# USB_to_Serial.net
KiCad netlist of a schematic drawn in Altium Designer
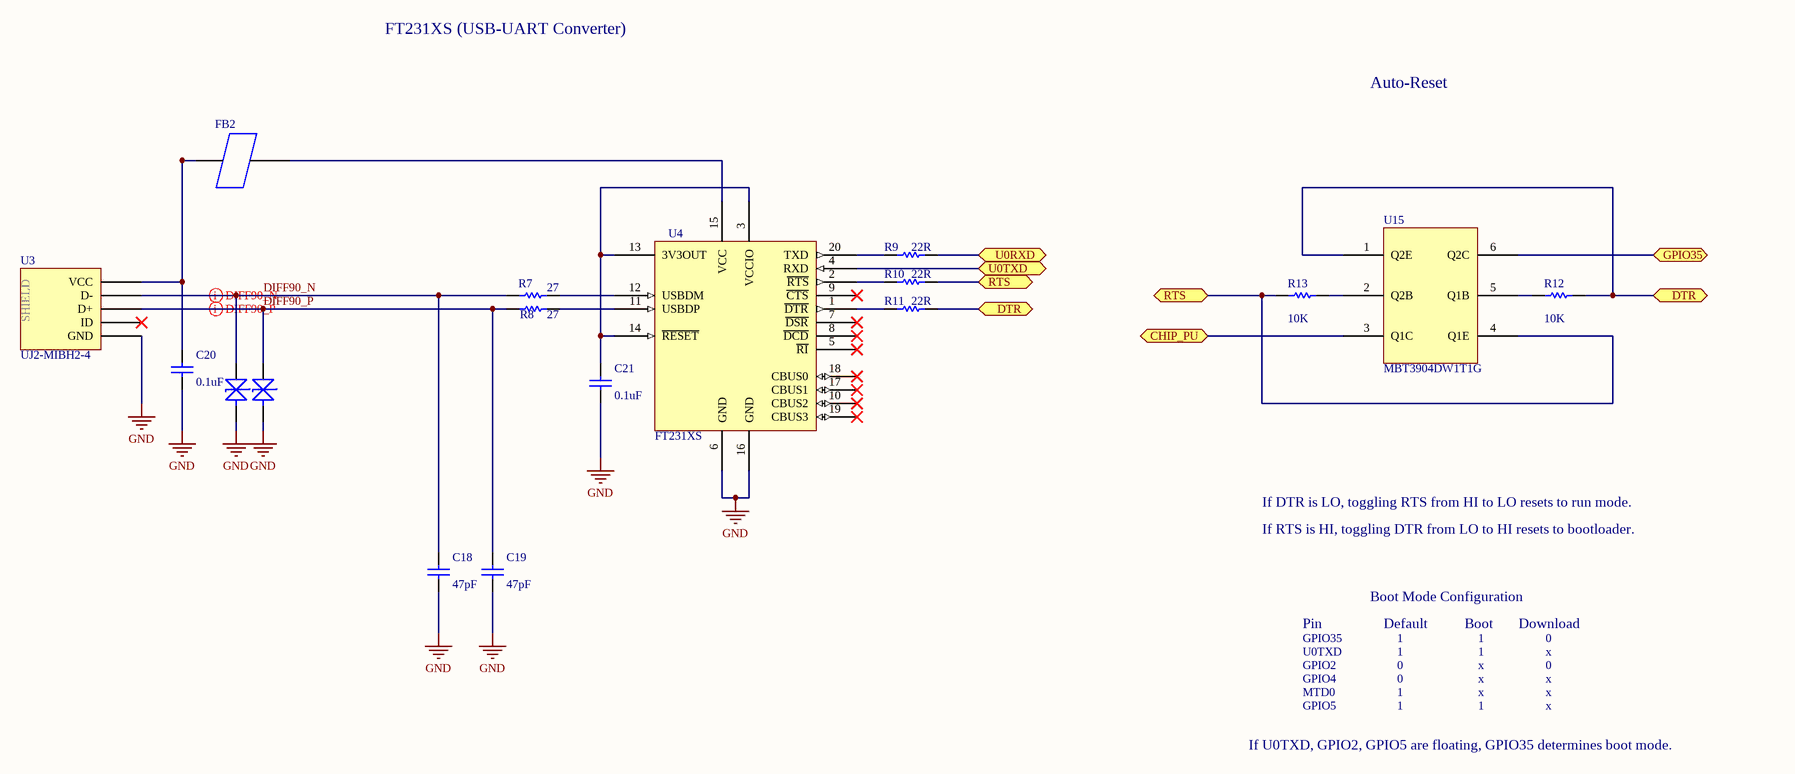
[diagram p0: USB to Serial.SchDoc]

(export (version "E")
  (design (tool "Eeschema 10.0.6"))
  (components
    (comp (ref "C18")
      (value "47pF")
      (footprint "0402")
      (description "Capacitor")
      (fields (field (name "Comment") "Cap") (field (name "PUBLISHER") "Altium Limited"))
      (libsource (lib "Miscellaneous Devices") (part "Cap"))
    )
    (comp (ref "C19")
      (value "47pF")
      (footprint "0402")
      (description "Capacitor")
      (fields (field (name "Comment") "Cap") (field (name "PUBLISHER") "Altium Limited"))
      (libsource (lib "Miscellaneous Devices") (part "Cap"))
    )
    (comp (ref "C20")
      (value "0.1uF")
      (footprint "1608[0603]")
      (description "Capacitor")
      (fields (field (name "Comment") "Cap") (field (name "PUBLISHER") "Altium Limited"))
      (libsource (lib "Miscellaneous Devices") (part "Cap"))
    )
    (comp (ref "C21")
      (value "0.1uF")
      (footprint "1608[0603]")
      (description "Capacitor")
      (fields (field (name "Comment") "Cap") (field (name "PUBLISHER") "Altium Limited"))
      (libsource (lib "Miscellaneous Devices") (part "Cap"))
    )
    (comp (ref "D2")
      (value "ESD7951ST5GOSCT-ND")
      (footprint "SODFL100X40-2N")
      (description "TVS Diode")
      (libsource (lib "Gas Monitor Components") (part "ESD7951S"))
    )
    (comp (ref "D3")
      (value "ESD7951ST5GOSCT-ND")
      (footprint "SODFL100X40-2N")
      (description "TVS Diode")
      (libsource (lib "Gas Monitor Components") (part "ESD7951S"))
    )
    (comp (ref "FB2")
      (value "Ferrite Bead")
      (footprint "MI0805K400R-10")
      (description "MI0805K400R-10")
      (libsource (lib "Gas Monitor Components") (part "Ferrite Bead"))
    )
    (comp (ref "R7")
      (value "27")
      (footprint "J1-0603")
      (description "Resistor")
      (fields (field (name "Comment") "Res1") (field (name "PUBLISHER") "Altium Limited"))
      (libsource (lib "Miscellaneous Devices") (part "Res1"))
    )
    (comp (ref "R8")
      (value "27")
      (footprint "J1-0603")
      (description "Resistor")
      (fields (field (name "Comment") "Res1") (field (name "PUBLISHER") "Altium Limited"))
      (libsource (lib "Miscellaneous Devices") (part "Res1"))
    )
    (comp (ref "R9")
      (value "22R")
      (footprint "6-0805_N")
      (description "Resistor")
      (fields (field (name "Comment") "Res1") (field (name "PUBLISHER") "Altium Limited"))
      (libsource (lib "Miscellaneous Devices") (part "Res1"))
    )
    (comp (ref "R10")
      (value "22R")
      (footprint "6-0805_N")
      (description "Resistor")
      (fields (field (name "Comment") "Res1") (field (name "PUBLISHER") "Altium Limited"))
      (libsource (lib "Miscellaneous Devices") (part "Res1"))
    )
    (comp (ref "R11")
      (value "22R")
      (footprint "6-0805_N")
      (description "Resistor")
      (fields (field (name "Comment") "Res1") (field (name "PUBLISHER") "Altium Limited"))
      (libsource (lib "Miscellaneous Devices") (part "Res1"))
    )
    (comp (ref "R12")
      (value "10K")
      (footprint "6-0805_N")
      (description "Resistor")
      (fields (field (name "Comment") "Res1") (field (name "PUBLISHER") "Altium Limited"))
      (libsource (lib "Miscellaneous Devices") (part "Res1"))
    )
    (comp (ref "R13")
      (value "10K")
      (footprint "6-0805_N")
      (description "Resistor")
      (fields (field (name "Comment") "Res1") (field (name "PUBLISHER") "Altium Limited"))
      (libsource (lib "Miscellaneous Devices") (part "Res1"))
    )
    (comp (ref "U3")
      (value "UJ2-MIBH2-4")
      (footprint "UJ2-MIBH2-4-SMT")
      (libsource (lib "Gas Monitor Components") (part "USB Shield"))
    )
    (comp (ref "U4")
      (value "FT231XS")
      (footprint "SOP64P1030X175-20N")
      (description "USB-UART Interface")
      (libsource (lib "Gas Monitor Components") (part "FT231XS"))
    )
    (comp (ref "U15")
      (value "MBT3904DW1T1G")
      (footprint "SOT65P210X110-6N")
      (description "Dual NPN Transistors")
      (libsource (lib "Gas Monitor Components") (part "MBT3904DW1"))
    )
  )
  (nets
    (net (code "1") (name "/CHIP_PU") (class "Default")
      (node (ref "U15") (pin "3") (pinfunction "Q1C_3") (pintype "passive"))
    )
    (net (code "2") (name "/DIFF90_N") (class "Default")
      (node (ref "C18") (pin "2") (pinfunction "2_2") (pintype "passive"))
      (node (ref "D2") (pin "2") (pinfunction "ANODE_2") (pintype "passive"))
      (node (ref "R7") (pin "1") (pinfunction "1_1") (pintype "passive"))
      (node (ref "U3") (pin "2") (pinfunction "D-_2") (pintype "passive"))
    )
    (net (code "3") (name "/DIFF90_P") (class "Default")
      (node (ref "C19") (pin "2") (pinfunction "2_2") (pintype "passive"))
      (node (ref "D3") (pin "2") (pinfunction "ANODE_2") (pintype "passive"))
      (node (ref "R8") (pin "1") (pinfunction "1_1") (pintype "passive"))
      (node (ref "U3") (pin "3") (pinfunction "D+_3") (pintype "passive"))
    )
    (net (code "4") (name "/DTR") (class "Default")
      (node (ref "R11") (pin "2") (pinfunction "2_2") (pintype "passive"))
      (node (ref "R12") (pin "2") (pinfunction "2_2") (pintype "passive"))
      (node (ref "U15") (pin "1") (pinfunction "Q2E_1") (pintype "passive"))
    )
    (net (code "5") (name "/GPIO35") (class "Default")
      (node (ref "U15") (pin "6") (pinfunction "Q2C_6") (pintype "passive"))
    )
    (net (code "6") (name "/RTS") (class "Default")
      (node (ref "R10") (pin "2") (pinfunction "2_2") (pintype "passive"))
      (node (ref "R13") (pin "1") (pinfunction "1_1") (pintype "passive"))
      (node (ref "U15") (pin "4") (pinfunction "Q1E_4") (pintype "passive"))
    )
    (net (code "7") (name "/U0RXD") (class "Default")
      (node (ref "R9") (pin "2") (pinfunction "2_2") (pintype "passive"))
    )
    (net (code "8") (name "/U0TXD") (class "Default")
      (node (ref "U4") (pin "4") (pinfunction "RXD_4") (pintype "input"))
    )
    (net (code "9") (name "GND") (class "Default")
      (node (ref "C18") (pin "1") (pinfunction "1_1") (pintype "passive"))
      (node (ref "C19") (pin "1") (pinfunction "1_1") (pintype "passive"))
      (node (ref "C20") (pin "1") (pinfunction "1_1") (pintype "passive"))
      (node (ref "C21") (pin "1") (pinfunction "1_1") (pintype "passive"))
      (node (ref "D2") (pin "1") (pinfunction "CATHODE_1") (pintype "passive"))
      (node (ref "D3") (pin "1") (pinfunction "CATHODE_1") (pintype "passive"))
      (node (ref "U3") (pin "5") (pinfunction "GND_5") (pintype "power_in"))
      (node (ref "U4") (pin "16") (pinfunction "GND_16") (pintype "power_in"))
      (node (ref "U4") (pin "6") (pinfunction "GND_6") (pintype "power_in"))
    )
    (net (code "10") (name "Net-(U3-VCC)") (class "Default")
      (node (ref "C20") (pin "2") (pinfunction "2_2") (pintype "passive"))
      (node (ref "FB2") (pin "1") (pinfunction "1_1") (pintype "passive"))
      (node (ref "U3") (pin "1") (pinfunction "VCC_1") (pintype "power_in"))
    )
    (net (code "11") (name "Net-(U4-3V3OUT)") (class "Default")
      (node (ref "C21") (pin "2") (pinfunction "2_2") (pintype "passive"))
      (node (ref "U4") (pin "13") (pinfunction "3V3OUT_13") (pintype "power_in"))
      (node (ref "U4") (pin "14") (pinfunction "~{RESET}_14") (pintype "input"))
      (node (ref "U4") (pin "3") (pinfunction "VCCIO_3") (pintype "passive"))
    )
    (net (code "12") (name "Net-(U4-TXD)") (class "Default")
      (node (ref "R9") (pin "1") (pinfunction "1_1") (pintype "passive"))
      (node (ref "U4") (pin "20") (pinfunction "TXD_20") (pintype "output"))
    )
    (net (code "13") (name "Net-(U4-USBDM)") (class "Default")
      (node (ref "R7") (pin "2") (pinfunction "2_2") (pintype "passive"))
      (node (ref "U4") (pin "12") (pinfunction "USBDM_12") (pintype "input"))
    )
    (net (code "14") (name "Net-(U4-USBDP)") (class "Default")
      (node (ref "R8") (pin "2") (pinfunction "2_2") (pintype "passive"))
      (node (ref "U4") (pin "11") (pinfunction "USBDP_11") (pintype "input"))
    )
    (net (code "15") (name "Net-(U4-VCC)") (class "Default")
      (node (ref "FB2") (pin "2") (pinfunction "2_2") (pintype "passive"))
      (node (ref "U4") (pin "15") (pinfunction "VCC_15") (pintype "power_in"))
    )
    (net (code "16") (name "Net-(U4-~{DTR})") (class "Default")
      (node (ref "R11") (pin "1") (pinfunction "1_1") (pintype "passive"))
      (node (ref "U4") (pin "1") (pinfunction "~{DTR}_1") (pintype "output"))
    )
    (net (code "17") (name "Net-(U4-~{RTS})") (class "Default")
      (node (ref "R10") (pin "1") (pinfunction "1_1") (pintype "passive"))
      (node (ref "U4") (pin "2") (pinfunction "~{RTS}_2") (pintype "output"))
    )
    (net (code "18") (name "Net-(U15-Q1B)") (class "Default")
      (node (ref "R12") (pin "1") (pinfunction "1_1") (pintype "passive"))
      (node (ref "U15") (pin "5") (pinfunction "Q1B_5") (pintype "passive"))
    )
    (net (code "19") (name "Net-(U15-Q2B)") (class "Default")
      (node (ref "R13") (pin "2") (pinfunction "2_2") (pintype "passive"))
      (node (ref "U15") (pin "2") (pinfunction "Q2B_2") (pintype "passive"))
    )
    (net (code "20") (name "unconnected-(U3-ID-Pad4)") (class "Default")
      (node (ref "U3") (pin "4") (pinfunction "ID_4") (pintype "passive+no_connect"))
    )
    (net (code "21") (name "unconnected-(U4-CBUS0-Pad18)") (class "Default")
      (node (ref "U4") (pin "18") (pinfunction "CBUS0_18") (pintype "bidirectional+no_connect"))
    )
    (net (code "22") (name "unconnected-(U4-CBUS1-Pad17)") (class "Default")
      (node (ref "U4") (pin "17") (pinfunction "CBUS1_17") (pintype "bidirectional+no_connect"))
    )
    (net (code "23") (name "unconnected-(U4-CBUS2-Pad10)") (class "Default")
      (node (ref "U4") (pin "10") (pinfunction "CBUS2_10") (pintype "bidirectional+no_connect"))
    )
    (net (code "24") (name "unconnected-(U4-CBUS3-Pad19)") (class "Default")
      (node (ref "U4") (pin "19") (pinfunction "CBUS3_19") (pintype "bidirectional+no_connect"))
    )
    (net (code "25") (name "unconnected-(U4-~{CTS}-Pad9)") (class "Default")
      (node (ref "U4") (pin "9") (pinfunction "~{CTS}_9") (pintype "passive+no_connect"))
    )
    (net (code "26") (name "unconnected-(U4-~{DCD}-Pad8)") (class "Default")
      (node (ref "U4") (pin "8") (pinfunction "~{DCD}_8") (pintype "passive+no_connect"))
    )
    (net (code "27") (name "unconnected-(U4-~{DSR}-Pad7)") (class "Default")
      (node (ref "U4") (pin "7") (pinfunction "~{DSR}_7") (pintype "passive+no_connect"))
    )
    (net (code "28") (name "unconnected-(U4-~{RI}-Pad5)") (class "Default")
      (node (ref "U4") (pin "5") (pinfunction "~{RI}_5") (pintype "passive+no_connect"))
    )
  )
)
